# tip120_controller.net
KiCad netlist of a schematic drawn in EAGLE
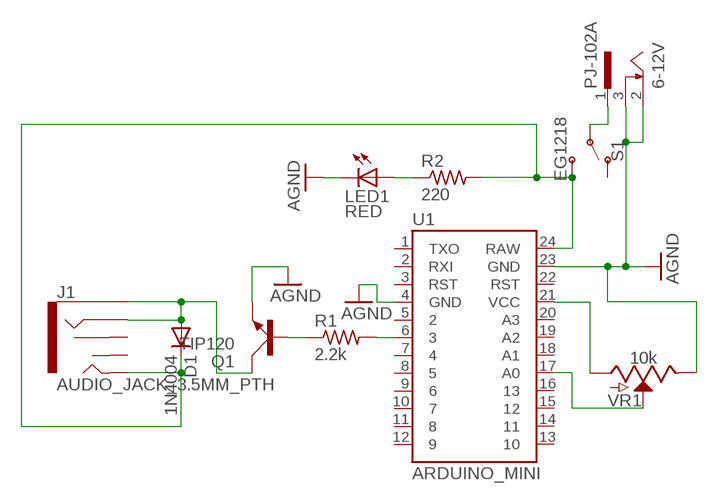
[diagram p0: schematic, sheet 1]

(export (version "E")
  (design (tool "Eeschema 10.0.6"))
  (components
    (comp (ref "D1")
      (value "1N4004")
      (footprint "eagle-import:DO41-10")
      (libsource (lib "eagle-import") (part "1N4004"))
    )
    (comp (ref "J1")
      (value "AUDIO_JACK_3.5MM_PTH")
      (footprint "eagle-import:AUDIO-JACK")
      (libsource (lib "eagle-import") (part "AUDIO_JACK_3.5MM_PTH"))
    )
    (comp (ref "LED1")
      (value "RED")
      (footprint "eagle-import:LED5MM")
      (libsource (lib "eagle-import") (part "LED5MM"))
    )
    (comp (ref "PJ-102A")
      (value "6-12V")
      (footprint "eagle-import:SCD-014-A")
      (libsource (lib "eagle-import") (part "SCD-014A"))
    )
    (comp (ref "Q1")
      (value "TIP120")
      (footprint "eagle-import:TO220AV")
      (libsource (lib "eagle-import") (part "TIP41C"))
    )
    (comp (ref "R1")
      (value "2.2k")
      (footprint "eagle-import:0204V")
      (libsource (lib "eagle-import") (part "R-US_0204/2V"))
    )
    (comp (ref "R2")
      (value "220")
      (footprint "eagle-import:0204V")
      (libsource (lib "eagle-import") (part "R-US_0204/2V"))
    )
    (comp (ref "S1")
      (value "EG1218")
      (footprint "eagle-import:SWITCH_SPDT_PTH_11.6X4.0MM_LOCK")
      (libsource (lib "eagle-import") (part "SWITCH-SPDT-PTH-11.6X4.0MM-LOCK"))
    )
    (comp (ref "U1")
      (value "ARDUINO_MINI")
      (footprint "eagle-import:ARDUINO_MINI")
      (libsource (lib "eagle-import") (part "ARDUINO_MINI"))
    )
    (comp (ref "VR1")
      (value "10k")
      (footprint "eagle-import:POT-PTH-ALPS")
      (libsource (lib "eagle-import") (part "POTENTIOMETER-PTH-9MM-1/20W-20%"))
    )
  )
  (nets
    (net (code "1") (name "AGND") (class "Default")
      (node (ref "LED1") (pin "K") (pinfunction "C_K") (pintype "passive"))
      (node (ref "PJ-102A") (pin "2") (pinfunction "2_2") (pintype "passive"))
      (node (ref "PJ-102A") (pin "3") (pinfunction "3_3") (pintype "passive"))
      (node (ref "Q1") (pin "E") (pinfunction "E_E") (pintype "passive"))
      (node (ref "U1") (pin "23") (pinfunction "GND_23") (pintype "bidirectional"))
      (node (ref "U1") (pin "4") (pinfunction "GND_4") (pintype "bidirectional"))
      (node (ref "VR1") (pin "P$1") (pinfunction "E_P$1") (pintype "passive"))
    )
    (net (code "2") (name "Net-(D1-PadA)") (class "Default")
      (node (ref "D1") (pin "A") (pinfunction "A_A") (pintype "passive"))
      (node (ref "J1") (pin "RING") (pinfunction "RING_RING") (pintype "bidirectional"))
      (node (ref "J1") (pin "SLEEVE") (pinfunction "SLEEVE_SLEEVE") (pintype "bidirectional"))
      (node (ref "Q1") (pin "C") (pinfunction "C_C") (pintype "passive"))
    )
    (net (code "3") (name "Net-(LED1-PadA)") (class "Default")
      (node (ref "LED1") (pin "A") (pinfunction "A_A") (pintype "passive"))
      (node (ref "R2") (pin "1") (pinfunction "1_1") (pintype "passive"))
    )
    (net (code "4") (name "Net-(Q1-PadB)") (class "Default")
      (node (ref "Q1") (pin "B") (pinfunction "B_B") (pintype "passive"))
      (node (ref "R1") (pin "1") (pinfunction "1_1") (pintype "passive"))
    )
    (net (code "5") (name "Net-(S1-P)") (class "Default")
      (node (ref "PJ-102A") (pin "1") (pinfunction "1_1") (pintype "passive"))
      (node (ref "S1") (pin "2") (pinfunction "P_2") (pintype "passive"))
    )
    (net (code "6") (name "Net-(S1-S)") (class "Default")
      (node (ref "D1") (pin "C") (pinfunction "C_C") (pintype "passive"))
      (node (ref "J1") (pin "TIP") (pinfunction "TIP_TIP") (pintype "bidirectional"))
      (node (ref "R2") (pin "2") (pinfunction "2_2") (pintype "passive"))
      (node (ref "S1") (pin "3") (pinfunction "S_3") (pintype "passive"))
      (node (ref "U1") (pin "24") (pinfunction "RAW_24") (pintype "bidirectional"))
    )
    (net (code "7") (name "Net-(U1-3)") (class "Default")
      (node (ref "R1") (pin "2") (pinfunction "2_2") (pintype "passive"))
      (node (ref "U1") (pin "6") (pinfunction "3_6") (pintype "bidirectional"))
    )
    (net (code "8") (name "Net-(U1-A0)") (class "Default")
      (node (ref "U1") (pin "17") (pinfunction "A0_17") (pintype "bidirectional"))
      (node (ref "VR1") (pin "P$2") (pinfunction "S_P$2") (pintype "passive"))
    )
    (net (code "9") (name "Net-(U1-VCC)") (class "Default")
      (node (ref "U1") (pin "21") (pinfunction "VCC_21") (pintype "bidirectional"))
      (node (ref "VR1") (pin "P$3") (pinfunction "A_P$3") (pintype "passive"))
    )
    (net (code "10") (name "unconnected-(J1-PadRSH)") (class "Default")
      (node (ref "J1") (pin "RSH") (pinfunction "RSH_RSH") (pintype "bidirectional"))
    )
    (net (code "11") (name "unconnected-(J1-PadTSH)") (class "Default")
      (node (ref "J1") (pin "TSH") (pinfunction "TSH_TSH") (pintype "bidirectional"))
    )
    (net (code "12") (name "unconnected-(S1-O-Pad1)") (class "Default")
      (node (ref "S1") (pin "1") (pinfunction "O_1") (pintype "passive"))
    )
    (net (code "13") (name "unconnected-(U1-2-Pad5)") (class "Default")
      (node (ref "U1") (pin "5") (pinfunction "2_5") (pintype "bidirectional"))
    )
    (net (code "14") (name "unconnected-(U1-4-Pad7)") (class "Default")
      (node (ref "U1") (pin "7") (pinfunction "4_7") (pintype "bidirectional"))
    )
    (net (code "15") (name "unconnected-(U1-5-Pad8)") (class "Default")
      (node (ref "U1") (pin "8") (pinfunction "5_8") (pintype "bidirectional"))
    )
    (net (code "16") (name "unconnected-(U1-6-Pad9)") (class "Default")
      (node (ref "U1") (pin "9") (pinfunction "6_9") (pintype "bidirectional"))
    )
    (net (code "17") (name "unconnected-(U1-7-Pad10)") (class "Default")
      (node (ref "U1") (pin "10") (pinfunction "7_10") (pintype "bidirectional"))
    )
    (net (code "18") (name "unconnected-(U1-8-Pad11)") (class "Default")
      (node (ref "U1") (pin "11") (pinfunction "8_11") (pintype "bidirectional"))
    )
    (net (code "19") (name "unconnected-(U1-9-Pad12)") (class "Default")
      (node (ref "U1") (pin "12") (pinfunction "9_12") (pintype "bidirectional"))
    )
    (net (code "20") (name "unconnected-(U1-10-Pad13)") (class "Default")
      (node (ref "U1") (pin "13") (pinfunction "10_13") (pintype "bidirectional"))
    )
    (net (code "21") (name "unconnected-(U1-11-Pad14)") (class "Default")
      (node (ref "U1") (pin "14") (pinfunction "11_14") (pintype "bidirectional"))
    )
    (net (code "22") (name "unconnected-(U1-12-Pad15)") (class "Default")
      (node (ref "U1") (pin "15") (pinfunction "12_15") (pintype "bidirectional"))
    )
    (net (code "23") (name "unconnected-(U1-13-Pad16)") (class "Default")
      (node (ref "U1") (pin "16") (pinfunction "13_16") (pintype "bidirectional"))
    )
    (net (code "24") (name "unconnected-(U1-A1-Pad18)") (class "Default")
      (node (ref "U1") (pin "18") (pinfunction "A1_18") (pintype "bidirectional"))
    )
    (net (code "25") (name "unconnected-(U1-A2-Pad19)") (class "Default")
      (node (ref "U1") (pin "19") (pinfunction "A2_19") (pintype "bidirectional"))
    )
    (net (code "26") (name "unconnected-(U1-A3-Pad20)") (class "Default")
      (node (ref "U1") (pin "20") (pinfunction "A3_20") (pintype "bidirectional"))
    )
    (net (code "27") (name "unconnected-(U1-RST-Pad3)") (class "Default")
      (node (ref "U1") (pin "3") (pinfunction "RST_3") (pintype "bidirectional"))
    )
    (net (code "28") (name "unconnected-(U1-RST-Pad22)") (class "Default")
      (node (ref "U1") (pin "22") (pinfunction "RST_22") (pintype "bidirectional"))
    )
    (net (code "29") (name "unconnected-(U1-RXI-Pad2)") (class "Default")
      (node (ref "U1") (pin "2") (pinfunction "RXI_2") (pintype "bidirectional"))
    )
    (net (code "30") (name "unconnected-(U1-TXO-Pad1)") (class "Default")
      (node (ref "U1") (pin "1") (pinfunction "TXO_1") (pintype "bidirectional"))
    )
  )
)
